# MCU.net
KiCad netlist of a schematic drawn in Altium Designer
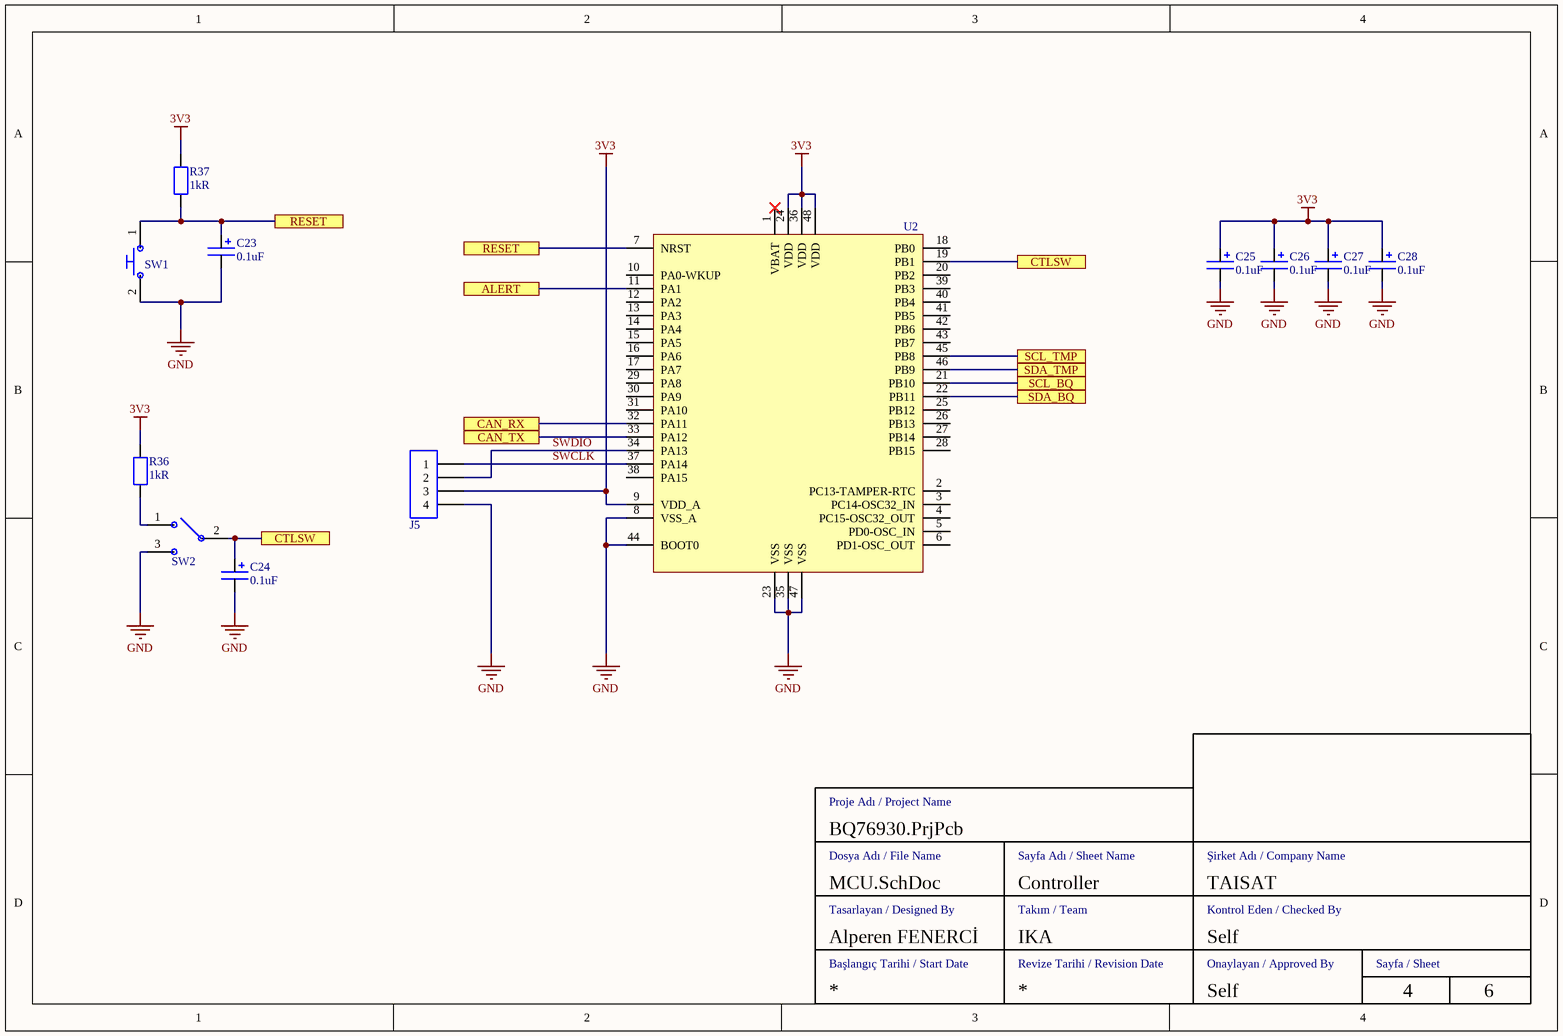
[diagram p0: MCU.SchDoc]

(export (version "E")
  (design (tool "Eeschema 10.0.6"))
  (components
    (comp (ref "C23")
      (value "0.1uF")
      (footprint "CAP 0603")
      (description "Multilayer Ceramic Capacitor")
      (fields (field (name "Comment") "CAP 0603"))
      (libsource (lib "Kaptanyums Lib") (part "CAP 0603"))
    )
    (comp (ref "C24")
      (value "0.1uF")
      (footprint "CAP 0603")
      (description "Multilayer Ceramic Capacitor")
      (fields (field (name "Comment") "CAP 0603"))
      (libsource (lib "Kaptanyums Lib") (part "CAP 0603"))
    )
    (comp (ref "C25")
      (value "0.1uF")
      (footprint "CAP 0603")
      (description "Multilayer Ceramic Capacitor")
      (fields (field (name "Comment") "CAP 0603"))
      (libsource (lib "Kaptanyums Lib") (part "CAP 0603"))
    )
    (comp (ref "C26")
      (value "0.1uF")
      (footprint "CAP 0603")
      (description "Multilayer Ceramic Capacitor")
      (fields (field (name "Comment") "CAP 0603"))
      (libsource (lib "Kaptanyums Lib") (part "CAP 0603"))
    )
    (comp (ref "C27")
      (value "0.1uF")
      (footprint "CAP 0603")
      (description "Multilayer Ceramic Capacitor")
      (fields (field (name "Comment") "CAP 0603"))
      (libsource (lib "Kaptanyums Lib") (part "CAP 0603"))
    )
    (comp (ref "C28")
      (value "0.1uF")
      (footprint "CAP 0603")
      (description "Multilayer Ceramic Capacitor")
      (fields (field (name "Comment") "CAP 0603"))
      (libsource (lib "Kaptanyums Lib") (part "CAP 0603"))
    )
    (comp (ref "J5")
      (value "146285-4")
      (footprint "HMATHT00C41")
      (description "Header for PCB")
      (libsource (lib "Kaptanyums Lib") (part "HMATHT00C41"))
    )
    (comp (ref "R36")
      (value "1kR")
      (footprint "RESISTOR 0603")
      (description "SMD Chip Resistor")
      (fields (field (name "Comment") "RES 0603"))
      (libsource (lib "Kaptanyums Lib") (part "RES 0603"))
    )
    (comp (ref "R37")
      (value "1kR")
      (footprint "RESISTOR 0603")
      (description "SMD Chip Resistor")
      (fields (field (name "Comment") "RES 0603"))
      (libsource (lib "Kaptanyums Lib") (part "RES 0603"))
    )
    (comp (ref "SW1")
      (value "DTSML-31R")
      (footprint "DTSML")
      (description "Switch")
      (libsource (lib "Kaptanyums Lib") (part "DTSML-31R"))
    )
    (comp (ref "SW2")
      (value "L-KLS7-SS-12F20A")
      (footprint "SPDT")
      (description "Switch")
      (libsource (lib "Kaptanyums Lib") (part "L-KLS7-SS-12F20A"))
    )
    (comp (ref "U2")
      (value "STM32F103x8")
      (footprint "LQFP48")
      (description "STM32 ARM Cortex M3")
      (libsource (lib "Kaptanyums Lib") (part "STM32F103x8"))
    )
  )
  (nets
    (net (code "1") (name "/ALERT") (class "Default")
      (node (ref "U2") (pin "11") (pinfunction "PA1_11") (pintype "passive"))
    )
    (net (code "2") (name "/CAN_RX") (class "Default")
      (node (ref "U2") (pin "32") (pinfunction "PA11_32") (pintype "passive"))
    )
    (net (code "3") (name "/CAN_TX") (class "Default")
      (node (ref "U2") (pin "33") (pinfunction "PA12_33") (pintype "passive"))
    )
    (net (code "4") (name "/CTLSW") (class "Default")
      (node (ref "C24") (pin "1") (pinfunction "1_1") (pintype "passive"))
      (node (ref "SW2") (pin "2") (pinfunction "2_2") (pintype "passive"))
      (node (ref "U2") (pin "19") (pinfunction "PB1_19") (pintype "passive"))
    )
    (net (code "5") (name "/RESET") (class "Default")
      (node (ref "C23") (pin "1") (pinfunction "1_1") (pintype "passive"))
      (node (ref "R37") (pin "1") (pinfunction "1_1") (pintype "passive"))
      (node (ref "SW1") (pin "1") (pinfunction "1_1") (pintype "passive"))
      (node (ref "U2") (pin "7") (pinfunction "NRST_7") (pintype "passive"))
    )
    (net (code "6") (name "/SCL_BQ") (class "Default")
      (node (ref "U2") (pin "21") (pinfunction "PB10_21") (pintype "passive"))
    )
    (net (code "7") (name "/SCL_TMP") (class "Default")
      (node (ref "U2") (pin "45") (pinfunction "PB8_45") (pintype "passive"))
    )
    (net (code "8") (name "/SDA_BQ") (class "Default")
      (node (ref "U2") (pin "22") (pinfunction "PB11_22") (pintype "passive"))
    )
    (net (code "9") (name "/SDA_TMP") (class "Default")
      (node (ref "U2") (pin "46") (pinfunction "PB9_46") (pintype "passive"))
    )
    (net (code "10") (name "/SWCLK") (class "Default")
      (node (ref "J5") (pin "1") (pinfunction "1_1") (pintype "passive"))
      (node (ref "U2") (pin "37") (pinfunction "PA14_37") (pintype "passive"))
    )
    (net (code "11") (name "/SWDIO") (class "Default")
      (node (ref "J5") (pin "2") (pinfunction "2_2") (pintype "passive"))
      (node (ref "U2") (pin "34") (pinfunction "PA13_34") (pintype "passive"))
    )
    (net (code "12") (name "3V3") (class "Default")
      (node (ref "C25") (pin "1") (pinfunction "1_1") (pintype "passive"))
      (node (ref "C26") (pin "1") (pinfunction "1_1") (pintype "passive"))
      (node (ref "C27") (pin "1") (pinfunction "1_1") (pintype "passive"))
      (node (ref "C28") (pin "1") (pinfunction "1_1") (pintype "passive"))
      (node (ref "J5") (pin "3") (pinfunction "3_3") (pintype "passive"))
      (node (ref "R36") (pin "2") (pinfunction "2_2") (pintype "passive"))
      (node (ref "R37") (pin "2") (pinfunction "2_2") (pintype "passive"))
      (node (ref "U2") (pin "24") (pinfunction "VDD_24") (pintype "passive"))
      (node (ref "U2") (pin "36") (pinfunction "VDD_36") (pintype "passive"))
      (node (ref "U2") (pin "48") (pinfunction "VDD_48") (pintype "passive"))
      (node (ref "U2") (pin "9") (pinfunction "VDD_A_9") (pintype "passive"))
    )
    (net (code "13") (name "GND") (class "Default")
      (node (ref "C23") (pin "2") (pinfunction "2_2") (pintype "passive"))
      (node (ref "C24") (pin "2") (pinfunction "2_2") (pintype "passive"))
      (node (ref "C25") (pin "2") (pinfunction "2_2") (pintype "passive"))
      (node (ref "C26") (pin "2") (pinfunction "2_2") (pintype "passive"))
      (node (ref "C27") (pin "2") (pinfunction "2_2") (pintype "passive"))
      (node (ref "C28") (pin "2") (pinfunction "2_2") (pintype "passive"))
      (node (ref "J5") (pin "4") (pinfunction "4_4") (pintype "passive"))
      (node (ref "SW1") (pin "2") (pinfunction "2_2") (pintype "passive"))
      (node (ref "SW2") (pin "3") (pinfunction "3_3") (pintype "passive"))
      (node (ref "U2") (pin "23") (pinfunction "VSS_23") (pintype "passive"))
      (node (ref "U2") (pin "35") (pinfunction "VSS_35") (pintype "passive"))
      (node (ref "U2") (pin "44") (pinfunction "BOOT0_44") (pintype "passive"))
      (node (ref "U2") (pin "47") (pinfunction "VSS_47") (pintype "passive"))
      (node (ref "U2") (pin "8") (pinfunction "VSS_A_8") (pintype "passive"))
    )
    (net (code "14") (name "Net-(R36-Pad1)") (class "Default")
      (node (ref "R36") (pin "1") (pinfunction "1_1") (pintype "passive"))
      (node (ref "SW2") (pin "1") (pinfunction "1_1") (pintype "passive"))
    )
    (net (code "15") (name "unconnected-(U2-PA0-WKUP-Pad10)") (class "Default")
      (node (ref "U2") (pin "10") (pinfunction "PA0-WKUP_10") (pintype "passive"))
    )
    (net (code "16") (name "unconnected-(U2-PA2-Pad12)") (class "Default")
      (node (ref "U2") (pin "12") (pinfunction "PA2_12") (pintype "passive"))
    )
    (net (code "17") (name "unconnected-(U2-PA3-Pad13)") (class "Default")
      (node (ref "U2") (pin "13") (pinfunction "PA3_13") (pintype "passive"))
    )
    (net (code "18") (name "unconnected-(U2-PA4-Pad14)") (class "Default")
      (node (ref "U2") (pin "14") (pinfunction "PA4_14") (pintype "passive"))
    )
    (net (code "19") (name "unconnected-(U2-PA5-Pad15)") (class "Default")
      (node (ref "U2") (pin "15") (pinfunction "PA5_15") (pintype "passive"))
    )
    (net (code "20") (name "unconnected-(U2-PA6-Pad16)") (class "Default")
      (node (ref "U2") (pin "16") (pinfunction "PA6_16") (pintype "passive"))
    )
    (net (code "21") (name "unconnected-(U2-PA7-Pad17)") (class "Default")
      (node (ref "U2") (pin "17") (pinfunction "PA7_17") (pintype "passive"))
    )
    (net (code "22") (name "unconnected-(U2-PA8-Pad29)") (class "Default")
      (node (ref "U2") (pin "29") (pinfunction "PA8_29") (pintype "passive"))
    )
    (net (code "23") (name "unconnected-(U2-PA9-Pad30)") (class "Default")
      (node (ref "U2") (pin "30") (pinfunction "PA9_30") (pintype "passive"))
    )
    (net (code "24") (name "unconnected-(U2-PA10-Pad31)") (class "Default")
      (node (ref "U2") (pin "31") (pinfunction "PA10_31") (pintype "passive"))
    )
    (net (code "25") (name "unconnected-(U2-PA15-Pad38)") (class "Default")
      (node (ref "U2") (pin "38") (pinfunction "PA15_38") (pintype "passive"))
    )
    (net (code "26") (name "unconnected-(U2-PB0-Pad18)") (class "Default")
      (node (ref "U2") (pin "18") (pinfunction "PB0_18") (pintype "passive"))
    )
    (net (code "27") (name "unconnected-(U2-PB2-Pad20)") (class "Default")
      (node (ref "U2") (pin "20") (pinfunction "PB2_20") (pintype "passive"))
    )
    (net (code "28") (name "unconnected-(U2-PB3-Pad39)") (class "Default")
      (node (ref "U2") (pin "39") (pinfunction "PB3_39") (pintype "passive"))
    )
    (net (code "29") (name "unconnected-(U2-PB4-Pad40)") (class "Default")
      (node (ref "U2") (pin "40") (pinfunction "PB4_40") (pintype "passive"))
    )
    (net (code "30") (name "unconnected-(U2-PB5-Pad41)") (class "Default")
      (node (ref "U2") (pin "41") (pinfunction "PB5_41") (pintype "passive"))
    )
    (net (code "31") (name "unconnected-(U2-PB6-Pad42)") (class "Default")
      (node (ref "U2") (pin "42") (pinfunction "PB6_42") (pintype "passive"))
    )
    (net (code "32") (name "unconnected-(U2-PB7-Pad43)") (class "Default")
      (node (ref "U2") (pin "43") (pinfunction "PB7_43") (pintype "passive"))
    )
    (net (code "33") (name "unconnected-(U2-PB12-Pad25)") (class "Default")
      (node (ref "U2") (pin "25") (pinfunction "PB12_25") (pintype "passive"))
    )
    (net (code "34") (name "unconnected-(U2-PB13-Pad26)") (class "Default")
      (node (ref "U2") (pin "26") (pinfunction "PB13_26") (pintype "passive"))
    )
    (net (code "35") (name "unconnected-(U2-PB14-Pad27)") (class "Default")
      (node (ref "U2") (pin "27") (pinfunction "PB14_27") (pintype "passive"))
    )
    (net (code "36") (name "unconnected-(U2-PB15-Pad28)") (class "Default")
      (node (ref "U2") (pin "28") (pinfunction "PB15_28") (pintype "passive"))
    )
    (net (code "37") (name "unconnected-(U2-PC13-TAMPER-RTC-Pad2)") (class "Default")
      (node (ref "U2") (pin "2") (pinfunction "PC13-TAMPER-RTC_2") (pintype "passive"))
    )
    (net (code "38") (name "unconnected-(U2-PC14-OSC32_IN-Pad3)") (class "Default")
      (node (ref "U2") (pin "3") (pinfunction "PC14-OSC32_IN_3") (pintype "passive"))
    )
    (net (code "39") (name "unconnected-(U2-PC15-OSC32_OUT-Pad4)") (class "Default")
      (node (ref "U2") (pin "4") (pinfunction "PC15-OSC32_OUT_4") (pintype "passive"))
    )
    (net (code "40") (name "unconnected-(U2-PD0-OSC_IN-Pad5)") (class "Default")
      (node (ref "U2") (pin "5") (pinfunction "PD0-OSC_IN_5") (pintype "passive"))
    )
    (net (code "41") (name "unconnected-(U2-PD1-OSC_OUT-Pad6)") (class "Default")
      (node (ref "U2") (pin "6") (pinfunction "PD1-OSC_OUT_6") (pintype "passive"))
    )
    (net (code "42") (name "unconnected-(U2-VBAT-Pad1)") (class "Default")
      (node (ref "U2") (pin "1") (pinfunction "VBAT_1") (pintype "passive+no_connect"))
    )
  )
)
